# sch1.net
KiCad netlist of a schematic drawn in EAGLE
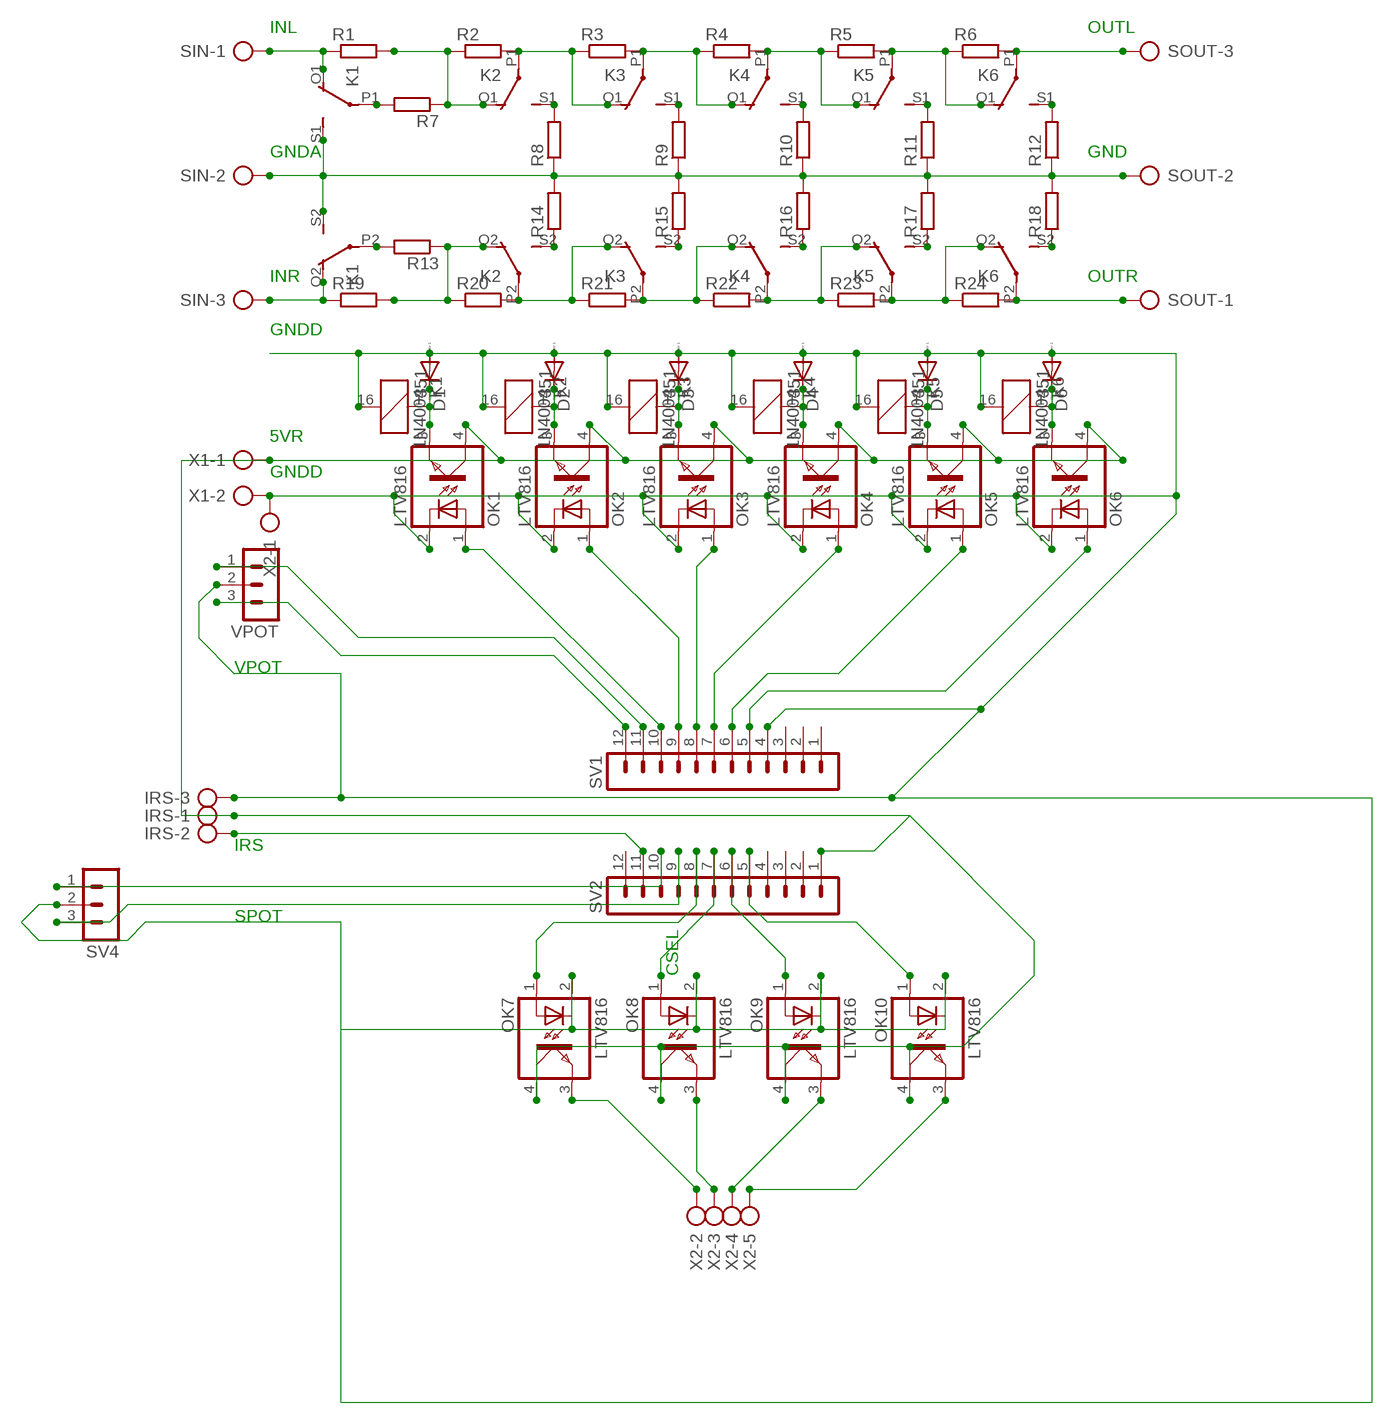
[diagram p0: schematic, sheet 1]

(export (version "E")
  (design (tool "Eeschema 10.0.6"))
  (components
    (comp (ref "D1")
      (value "1N4004")
      (footprint "eagle-import:DO41-10")
      (libsource (lib "eagle-import") (part "1N4004"))
    )
    (comp (ref "D2")
      (value "1N4004")
      (footprint "eagle-import:DO41-10")
      (libsource (lib "eagle-import") (part "1N4004"))
    )
    (comp (ref "D3")
      (value "1N4004")
      (footprint "eagle-import:DO41-10")
      (libsource (lib "eagle-import") (part "1N4004"))
    )
    (comp (ref "D4")
      (value "1N4004")
      (footprint "eagle-import:DO41-10")
      (libsource (lib "eagle-import") (part "1N4004"))
    )
    (comp (ref "D5")
      (value "1N4004")
      (footprint "eagle-import:DO41-10")
      (libsource (lib "eagle-import") (part "1N4004"))
    )
    (comp (ref "D6")
      (value "1N4004")
      (footprint "eagle-import:DO41-10")
      (libsource (lib "eagle-import") (part "1N4004"))
    )
    (comp (ref "IRS")
      (value "AK500/3")
      (footprint "eagle-import:AK500_3")
      (libsource (lib "eagle-import") (part "AK500/3"))
    )
    (comp (ref "K1")
      (value "351")
      (footprint "eagle-import:351")
      (libsource (lib "eagle-import") (part "351"))
    )
    (comp (ref "K2")
      (value "351")
      (footprint "eagle-import:351")
      (libsource (lib "eagle-import") (part "351"))
    )
    (comp (ref "K3")
      (value "351")
      (footprint "eagle-import:351")
      (libsource (lib "eagle-import") (part "351"))
    )
    (comp (ref "K4")
      (value "351")
      (footprint "eagle-import:351")
      (libsource (lib "eagle-import") (part "351"))
    )
    (comp (ref "K5")
      (value "351")
      (footprint "eagle-import:351")
      (libsource (lib "eagle-import") (part "351"))
    )
    (comp (ref "K6")
      (value "351")
      (footprint "eagle-import:351")
      (libsource (lib "eagle-import") (part "351"))
    )
    (comp (ref "OK1")
      (value "LTV816")
      (footprint "eagle-import:DIL04")
      (libsource (lib "eagle-import") (part "LTV816"))
    )
    (comp (ref "OK2")
      (value "LTV816")
      (footprint "eagle-import:DIL04")
      (libsource (lib "eagle-import") (part "LTV816"))
    )
    (comp (ref "OK3")
      (value "LTV816")
      (footprint "eagle-import:DIL04")
      (libsource (lib "eagle-import") (part "LTV816"))
    )
    (comp (ref "OK4")
      (value "LTV816")
      (footprint "eagle-import:DIL04")
      (libsource (lib "eagle-import") (part "LTV816"))
    )
    (comp (ref "OK5")
      (value "LTV816")
      (footprint "eagle-import:DIL04")
      (libsource (lib "eagle-import") (part "LTV816"))
    )
    (comp (ref "OK6")
      (value "LTV816")
      (footprint "eagle-import:DIL04")
      (libsource (lib "eagle-import") (part "LTV816"))
    )
    (comp (ref "OK7")
      (value "LTV816")
      (footprint "eagle-import:DIL04")
      (libsource (lib "eagle-import") (part "LTV816"))
    )
    (comp (ref "OK8")
      (value "LTV816")
      (footprint "eagle-import:DIL04")
      (libsource (lib "eagle-import") (part "LTV816"))
    )
    (comp (ref "OK9")
      (value "LTV816")
      (footprint "eagle-import:DIL04")
      (libsource (lib "eagle-import") (part "LTV816"))
    )
    (comp (ref "OK10")
      (value "LTV816")
      (footprint "eagle-import:DIL04")
      (libsource (lib "eagle-import") (part "LTV816"))
    )
    (comp (ref "R1")
      (value "R-EU_0204/7")
      (footprint "eagle-import:0204_7")
      (libsource (lib "eagle-import") (part "R-EU_0204/7"))
    )
    (comp (ref "R2")
      (value "R-EU_0204/7")
      (footprint "eagle-import:0204_7")
      (libsource (lib "eagle-import") (part "R-EU_0204/7"))
    )
    (comp (ref "R3")
      (value "R-EU_0204/7")
      (footprint "eagle-import:0204_7")
      (libsource (lib "eagle-import") (part "R-EU_0204/7"))
    )
    (comp (ref "R4")
      (value "R-EU_0204/7")
      (footprint "eagle-import:0204_7")
      (libsource (lib "eagle-import") (part "R-EU_0204/7"))
    )
    (comp (ref "R5")
      (value "R-EU_0204/7")
      (footprint "eagle-import:0204_7")
      (libsource (lib "eagle-import") (part "R-EU_0204/7"))
    )
    (comp (ref "R6")
      (value "R-EU_0204/7")
      (footprint "eagle-import:0204_7")
      (libsource (lib "eagle-import") (part "R-EU_0204/7"))
    )
    (comp (ref "R7")
      (value "R-EU_0204/7")
      (footprint "eagle-import:0204_7")
      (libsource (lib "eagle-import") (part "R-EU_0204/7"))
    )
    (comp (ref "R8")
      (value "R-EU_0204/7")
      (footprint "eagle-import:0204_7")
      (libsource (lib "eagle-import") (part "R-EU_0204/7"))
    )
    (comp (ref "R9")
      (value "R-EU_0204/7")
      (footprint "eagle-import:0204_7")
      (libsource (lib "eagle-import") (part "R-EU_0204/7"))
    )
    (comp (ref "R10")
      (value "R-EU_0204/7")
      (footprint "eagle-import:0204_7")
      (libsource (lib "eagle-import") (part "R-EU_0204/7"))
    )
    (comp (ref "R11")
      (value "R-EU_0204/7")
      (footprint "eagle-import:0204_7")
      (libsource (lib "eagle-import") (part "R-EU_0204/7"))
    )
    (comp (ref "R12")
      (value "R-EU_0204/7")
      (footprint "eagle-import:0204_7")
      (libsource (lib "eagle-import") (part "R-EU_0204/7"))
    )
    (comp (ref "R13")
      (value "R-EU_0204/7")
      (footprint "eagle-import:0204_7")
      (libsource (lib "eagle-import") (part "R-EU_0204/7"))
    )
    (comp (ref "R14")
      (value "R-EU_0204/7")
      (footprint "eagle-import:0204_7")
      (libsource (lib "eagle-import") (part "R-EU_0204/7"))
    )
    (comp (ref "R15")
      (value "R-EU_0204/7")
      (footprint "eagle-import:0204_7")
      (libsource (lib "eagle-import") (part "R-EU_0204/7"))
    )
    (comp (ref "R16")
      (value "R-EU_0204/7")
      (footprint "eagle-import:0204_7")
      (libsource (lib "eagle-import") (part "R-EU_0204/7"))
    )
    (comp (ref "R17")
      (value "R-EU_0204/7")
      (footprint "eagle-import:0204_7")
      (libsource (lib "eagle-import") (part "R-EU_0204/7"))
    )
    (comp (ref "R18")
      (value "R-EU_0204/7")
      (footprint "eagle-import:0204_7")
      (libsource (lib "eagle-import") (part "R-EU_0204/7"))
    )
    (comp (ref "R19")
      (value "R-EU_0204/7")
      (footprint "eagle-import:0204_7")
      (libsource (lib "eagle-import") (part "R-EU_0204/7"))
    )
    (comp (ref "R20")
      (value "R-EU_0204/7")
      (footprint "eagle-import:0204_7")
      (libsource (lib "eagle-import") (part "R-EU_0204/7"))
    )
    (comp (ref "R21")
      (value "R-EU_0204/7")
      (footprint "eagle-import:0204_7")
      (libsource (lib "eagle-import") (part "R-EU_0204/7"))
    )
    (comp (ref "R22")
      (value "R-EU_0204/7")
      (footprint "eagle-import:0204_7")
      (libsource (lib "eagle-import") (part "R-EU_0204/7"))
    )
    (comp (ref "R23")
      (value "R-EU_0204/7")
      (footprint "eagle-import:0204_7")
      (libsource (lib "eagle-import") (part "R-EU_0204/7"))
    )
    (comp (ref "R24")
      (value "R-EU_0204/7")
      (footprint "eagle-import:0204_7")
      (libsource (lib "eagle-import") (part "R-EU_0204/7"))
    )
    (comp (ref "SIN")
      (value "AK500/3")
      (footprint "eagle-import:AK500_3")
      (libsource (lib "eagle-import") (part "AK500/3"))
    )
    (comp (ref "SOUT")
      (value "AK500/3")
      (footprint "eagle-import:AK500_3")
      (libsource (lib "eagle-import") (part "AK500/3"))
    )
    (comp (ref "SV1")
      (value "MA12-1")
      (footprint "eagle-import:MA12-1")
      (libsource (lib "eagle-import") (part "MA12-1"))
    )
    (comp (ref "SV2")
      (value "MA12-1")
      (footprint "eagle-import:MA12-1")
      (libsource (lib "eagle-import") (part "MA12-1"))
    )
    (comp (ref "SV4")
      (value "MA03-1")
      (footprint "eagle-import:MA03-1")
      (libsource (lib "eagle-import") (part "MA03-1"))
    )
    (comp (ref "VPOT")
      (value "MA03-1")
      (footprint "eagle-import:MA03-1")
      (libsource (lib "eagle-import") (part "MA03-1"))
    )
    (comp (ref "X1")
      (value "AK500/2")
      (footprint "eagle-import:AK500_2")
      (libsource (lib "eagle-import") (part "AK500/2"))
    )
    (comp (ref "X2")
      (value "AK500/5")
      (footprint "eagle-import:AK500_5")
      (libsource (lib "eagle-import") (part "AK500/5"))
    )
  )
  (nets
    (net (code "1") (name "Net-(IRSA-KL)") (class "Default")
      (node (ref "IRS") (pin "1") (pinfunction "KL_1") (pintype "passive"))
      (node (ref "OK1") (pin "4") (pinfunction "COL_4") (pintype "passive"))
      (node (ref "OK10") (pin "4") (pinfunction "COL_4") (pintype "passive"))
      (node (ref "OK2") (pin "4") (pinfunction "COL_4") (pintype "passive"))
      (node (ref "OK3") (pin "4") (pinfunction "COL_4") (pintype "passive"))
      (node (ref "OK4") (pin "4") (pinfunction "COL_4") (pintype "passive"))
      (node (ref "OK5") (pin "4") (pinfunction "COL_4") (pintype "passive"))
      (node (ref "OK6") (pin "4") (pinfunction "COL_4") (pintype "passive"))
      (node (ref "OK7") (pin "4") (pinfunction "COL_4") (pintype "passive"))
      (node (ref "OK8") (pin "4") (pinfunction "COL_4") (pintype "passive"))
      (node (ref "OK9") (pin "4") (pinfunction "COL_4") (pintype "passive"))
      (node (ref "SV2") (pin "1") (pinfunction "1_1") (pintype "passive"))
      (node (ref "X1") (pin "1") (pinfunction "KL_1") (pintype "passive"))
    )
    (net (code "2") (name "Net-(IRSB-KL)") (class "Default")
      (node (ref "IRS") (pin "2") (pinfunction "KL_2") (pintype "passive"))
      (node (ref "SV2") (pin "11") (pinfunction "11_11") (pintype "passive"))
    )
    (net (code "3") (name "Net-(IRSC-KL)") (class "Default")
      (node (ref "D1") (pin "A") (pinfunction "A_A") (pintype "passive"))
      (node (ref "D2") (pin "A") (pinfunction "A_A") (pintype "passive"))
      (node (ref "D3") (pin "A") (pinfunction "A_A") (pintype "passive"))
      (node (ref "D4") (pin "A") (pinfunction "A_A") (pintype "passive"))
      (node (ref "D5") (pin "A") (pinfunction "A_A") (pintype "passive"))
      (node (ref "D6") (pin "A") (pinfunction "A_A") (pintype "passive"))
      (node (ref "IRS") (pin "3") (pinfunction "KL_3") (pintype "passive"))
      (node (ref "K1") (pin "16") (pinfunction "2_16") (pintype "passive"))
      (node (ref "K2") (pin "16") (pinfunction "2_16") (pintype "passive"))
      (node (ref "K3") (pin "16") (pinfunction "2_16") (pintype "passive"))
      (node (ref "K4") (pin "16") (pinfunction "2_16") (pintype "passive"))
      (node (ref "K5") (pin "16") (pinfunction "2_16") (pintype "passive"))
      (node (ref "K6") (pin "16") (pinfunction "2_16") (pintype "passive"))
      (node (ref "OK1") (pin "2") (pinfunction "C_2") (pintype "passive"))
      (node (ref "OK10") (pin "2") (pinfunction "C_2") (pintype "passive"))
      (node (ref "OK2") (pin "2") (pinfunction "C_2") (pintype "passive"))
      (node (ref "OK3") (pin "2") (pinfunction "C_2") (pintype "passive"))
      (node (ref "OK4") (pin "2") (pinfunction "C_2") (pintype "passive"))
      (node (ref "OK5") (pin "2") (pinfunction "C_2") (pintype "passive"))
      (node (ref "OK6") (pin "2") (pinfunction "C_2") (pintype "passive"))
      (node (ref "OK7") (pin "2") (pinfunction "C_2") (pintype "passive"))
      (node (ref "OK8") (pin "2") (pinfunction "C_2") (pintype "passive"))
      (node (ref "OK9") (pin "2") (pinfunction "C_2") (pintype "passive"))
      (node (ref "SV1") (pin "4") (pinfunction "4_4") (pintype "passive"))
      (node (ref "SV4") (pin "2") (pinfunction "2_2") (pintype "passive"))
      (node (ref "VPOT") (pin "2") (pinfunction "2_2") (pintype "passive"))
      (node (ref "X1") (pin "2") (pinfunction "KL_2") (pintype "passive"))
      (node (ref "X2") (pin "1") (pinfunction "KL_1") (pintype "passive"))
    )
    (net (code "4") (name "Net-(K1B-O)") (class "Default")
      (node (ref "K1") (pin "O1") (pinfunction "O_O1") (pintype "passive"))
      (node (ref "R1") (pin "1") (pinfunction "1_1") (pintype "passive"))
      (node (ref "SIN") (pin "1") (pinfunction "KL_1") (pintype "passive"))
    )
    (net (code "5") (name "Net-(K1B-P)") (class "Default")
      (node (ref "K1") (pin "P1") (pinfunction "P_P1") (pintype "passive"))
      (node (ref "R7") (pin "2") (pinfunction "2_2") (pintype "passive"))
    )
    (net (code "6") (name "Net-(K1B-S)") (class "Default")
      (node (ref "K1") (pin "S1") (pinfunction "S_S1") (pintype "passive"))
      (node (ref "K1") (pin "S2") (pinfunction "S_S2") (pintype "passive"))
      (node (ref "R10") (pin "1") (pinfunction "1_1") (pintype "passive"))
      (node (ref "R11") (pin "1") (pinfunction "1_1") (pintype "passive"))
      (node (ref "R12") (pin "1") (pinfunction "1_1") (pintype "passive"))
      (node (ref "R14") (pin "2") (pinfunction "2_2") (pintype "passive"))
      (node (ref "R15") (pin "2") (pinfunction "2_2") (pintype "passive"))
      (node (ref "R16") (pin "2") (pinfunction "2_2") (pintype "passive"))
      (node (ref "R17") (pin "2") (pinfunction "2_2") (pintype "passive"))
      (node (ref "R18") (pin "2") (pinfunction "2_2") (pintype "passive"))
      (node (ref "R8") (pin "1") (pinfunction "1_1") (pintype "passive"))
      (node (ref "R9") (pin "1") (pinfunction "1_1") (pintype "passive"))
      (node (ref "SIN") (pin "2") (pinfunction "KL_2") (pintype "passive"))
      (node (ref "SOUT") (pin "2") (pinfunction "KL_2") (pintype "passive"))
    )
    (net (code "7") (name "Net-(K1C-O)") (class "Default")
      (node (ref "K1") (pin "O2") (pinfunction "O_O2") (pintype "passive"))
      (node (ref "R19") (pin "1") (pinfunction "1_1") (pintype "passive"))
      (node (ref "SIN") (pin "3") (pinfunction "KL_3") (pintype "passive"))
    )
    (net (code "8") (name "Net-(K1C-P)") (class "Default")
      (node (ref "K1") (pin "P2") (pinfunction "P_P2") (pintype "passive"))
      (node (ref "R13") (pin "2") (pinfunction "2_2") (pintype "passive"))
    )
    (net (code "9") (name "Net-(K2B-O)") (class "Default")
      (node (ref "K2") (pin "O1") (pinfunction "O_O1") (pintype "passive"))
      (node (ref "R1") (pin "2") (pinfunction "2_2") (pintype "passive"))
      (node (ref "R2") (pin "1") (pinfunction "1_1") (pintype "passive"))
      (node (ref "R7") (pin "1") (pinfunction "1_1") (pintype "passive"))
    )
    (net (code "10") (name "Net-(K2B-P)") (class "Default")
      (node (ref "K2") (pin "P1") (pinfunction "P_P1") (pintype "passive"))
      (node (ref "K3") (pin "O1") (pinfunction "O_O1") (pintype "passive"))
      (node (ref "R2") (pin "2") (pinfunction "2_2") (pintype "passive"))
      (node (ref "R3") (pin "1") (pinfunction "1_1") (pintype "passive"))
    )
    (net (code "11") (name "Net-(K2B-S)") (class "Default")
      (node (ref "K2") (pin "S1") (pinfunction "S_S1") (pintype "passive"))
      (node (ref "R8") (pin "2") (pinfunction "2_2") (pintype "passive"))
    )
    (net (code "12") (name "Net-(K2C-O)") (class "Default")
      (node (ref "K2") (pin "O2") (pinfunction "O_O2") (pintype "passive"))
      (node (ref "R13") (pin "1") (pinfunction "1_1") (pintype "passive"))
      (node (ref "R19") (pin "2") (pinfunction "2_2") (pintype "passive"))
      (node (ref "R20") (pin "1") (pinfunction "1_1") (pintype "passive"))
    )
    (net (code "13") (name "Net-(K2C-P)") (class "Default")
      (node (ref "K2") (pin "P2") (pinfunction "P_P2") (pintype "passive"))
      (node (ref "K3") (pin "O2") (pinfunction "O_O2") (pintype "passive"))
      (node (ref "R20") (pin "2") (pinfunction "2_2") (pintype "passive"))
      (node (ref "R21") (pin "1") (pinfunction "1_1") (pintype "passive"))
    )
    (net (code "14") (name "Net-(K2C-S)") (class "Default")
      (node (ref "K2") (pin "S2") (pinfunction "S_S2") (pintype "passive"))
      (node (ref "R14") (pin "1") (pinfunction "1_1") (pintype "passive"))
    )
    (net (code "15") (name "Net-(K3B-P)") (class "Default")
      (node (ref "K3") (pin "P1") (pinfunction "P_P1") (pintype "passive"))
      (node (ref "K4") (pin "O1") (pinfunction "O_O1") (pintype "passive"))
      (node (ref "R3") (pin "2") (pinfunction "2_2") (pintype "passive"))
      (node (ref "R4") (pin "1") (pinfunction "1_1") (pintype "passive"))
    )
    (net (code "16") (name "Net-(K3B-S)") (class "Default")
      (node (ref "K3") (pin "S1") (pinfunction "S_S1") (pintype "passive"))
      (node (ref "R9") (pin "2") (pinfunction "2_2") (pintype "passive"))
    )
    (net (code "17") (name "Net-(K3C-P)") (class "Default")
      (node (ref "K3") (pin "P2") (pinfunction "P_P2") (pintype "passive"))
      (node (ref "K4") (pin "O2") (pinfunction "O_O2") (pintype "passive"))
      (node (ref "R21") (pin "2") (pinfunction "2_2") (pintype "passive"))
      (node (ref "R22") (pin "1") (pinfunction "1_1") (pintype "passive"))
    )
    (net (code "18") (name "Net-(K3C-S)") (class "Default")
      (node (ref "K3") (pin "S2") (pinfunction "S_S2") (pintype "passive"))
      (node (ref "R15") (pin "1") (pinfunction "1_1") (pintype "passive"))
    )
    (net (code "19") (name "Net-(K4B-P)") (class "Default")
      (node (ref "K4") (pin "P1") (pinfunction "P_P1") (pintype "passive"))
      (node (ref "K5") (pin "O1") (pinfunction "O_O1") (pintype "passive"))
      (node (ref "R4") (pin "2") (pinfunction "2_2") (pintype "passive"))
      (node (ref "R5") (pin "1") (pinfunction "1_1") (pintype "passive"))
    )
    (net (code "20") (name "Net-(K4B-S)") (class "Default")
      (node (ref "K4") (pin "S1") (pinfunction "S_S1") (pintype "passive"))
      (node (ref "R10") (pin "2") (pinfunction "2_2") (pintype "passive"))
    )
    (net (code "21") (name "Net-(K4C-P)") (class "Default")
      (node (ref "K4") (pin "P2") (pinfunction "P_P2") (pintype "passive"))
      (node (ref "K5") (pin "O2") (pinfunction "O_O2") (pintype "passive"))
      (node (ref "R22") (pin "2") (pinfunction "2_2") (pintype "passive"))
      (node (ref "R23") (pin "1") (pinfunction "1_1") (pintype "passive"))
    )
    (net (code "22") (name "Net-(K4C-S)") (class "Default")
      (node (ref "K4") (pin "S2") (pinfunction "S_S2") (pintype "passive"))
      (node (ref "R16") (pin "1") (pinfunction "1_1") (pintype "passive"))
    )
    (net (code "23") (name "Net-(K5B-P)") (class "Default")
      (node (ref "K5") (pin "P1") (pinfunction "P_P1") (pintype "passive"))
      (node (ref "K6") (pin "O1") (pinfunction "O_O1") (pintype "passive"))
      (node (ref "R5") (pin "2") (pinfunction "2_2") (pintype "passive"))
      (node (ref "R6") (pin "1") (pinfunction "1_1") (pintype "passive"))
    )
    (net (code "24") (name "Net-(K5B-S)") (class "Default")
      (node (ref "K5") (pin "S1") (pinfunction "S_S1") (pintype "passive"))
      (node (ref "R11") (pin "2") (pinfunction "2_2") (pintype "passive"))
    )
    (net (code "25") (name "Net-(K5C-P)") (class "Default")
      (node (ref "K5") (pin "P2") (pinfunction "P_P2") (pintype "passive"))
      (node (ref "K6") (pin "O2") (pinfunction "O_O2") (pintype "passive"))
      (node (ref "R23") (pin "2") (pinfunction "2_2") (pintype "passive"))
      (node (ref "R24") (pin "1") (pinfunction "1_1") (pintype "passive"))
    )
    (net (code "26") (name "Net-(K5C-S)") (class "Default")
      (node (ref "K5") (pin "S2") (pinfunction "S_S2") (pintype "passive"))
      (node (ref "R17") (pin "1") (pinfunction "1_1") (pintype "passive"))
    )
    (net (code "27") (name "Net-(K6B-P)") (class "Default")
      (node (ref "K6") (pin "P1") (pinfunction "P_P1") (pintype "passive"))
      (node (ref "R6") (pin "2") (pinfunction "2_2") (pintype "passive"))
      (node (ref "SOUT") (pin "3") (pinfunction "KL_3") (pintype "passive"))
    )
    (net (code "28") (name "Net-(K6B-S)") (class "Default")
      (node (ref "K6") (pin "S1") (pinfunction "S_S1") (pintype "passive"))
      (node (ref "R12") (pin "2") (pinfunction "2_2") (pintype "passive"))
    )
    (net (code "29") (name "Net-(K6C-P)") (class "Default")
      (node (ref "K6") (pin "P2") (pinfunction "P_P2") (pintype "passive"))
      (node (ref "R24") (pin "2") (pinfunction "2_2") (pintype "passive"))
      (node (ref "SOUT") (pin "1") (pinfunction "KL_1") (pintype "passive"))
    )
    (net (code "30") (name "Net-(K6C-S)") (class "Default")
      (node (ref "K6") (pin "S2") (pinfunction "S_S2") (pintype "passive"))
      (node (ref "R18") (pin "1") (pinfunction "1_1") (pintype "passive"))
    )
    (net (code "31") (name "Net-(OK1-A)") (class "Default")
      (node (ref "OK1") (pin "1") (pinfunction "A_1") (pintype "passive"))
      (node (ref "SV1") (pin "10") (pinfunction "10_10") (pintype "passive"))
    )
    (net (code "32") (name "Net-(OK1-EMIT)") (class "Default")
      (node (ref "D1") (pin "C") (pinfunction "C_C") (pintype "passive"))
      (node (ref "K1") (pin "1") (pinfunction "1_1") (pintype "passive"))
      (node (ref "OK1") (pin "3") (pinfunction "EMIT_3") (pintype "passive"))
    )
    (net (code "33") (name "Net-(OK2-A)") (class "Default")
      (node (ref "OK2") (pin "1") (pinfunction "A_1") (pintype "passive"))
      (node (ref "SV1") (pin "9") (pinfunction "9_9") (pintype "passive"))
    )
    (net (code "34") (name "Net-(OK2-EMIT)") (class "Default")
      (node (ref "D2") (pin "C") (pinfunction "C_C") (pintype "passive"))
      (node (ref "K2") (pin "1") (pinfunction "1_1") (pintype "passive"))
      (node (ref "OK2") (pin "3") (pinfunction "EMIT_3") (pintype "passive"))
    )
    (net (code "35") (name "Net-(OK3-A)") (class "Default")
      (node (ref "OK3") (pin "1") (pinfunction "A_1") (pintype "passive"))
      (node (ref "SV1") (pin "8") (pinfunction "8_8") (pintype "passive"))
    )
    (net (code "36") (name "Net-(OK3-EMIT)") (class "Default")
      (node (ref "D3") (pin "C") (pinfunction "C_C") (pintype "passive"))
      (node (ref "K3") (pin "1") (pinfunction "1_1") (pintype "passive"))
      (node (ref "OK3") (pin "3") (pinfunction "EMIT_3") (pintype "passive"))
    )
    (net (code "37") (name "Net-(OK4-A)") (class "Default")
      (node (ref "OK4") (pin "1") (pinfunction "A_1") (pintype "passive"))
      (node (ref "SV1") (pin "7") (pinfunction "7_7") (pintype "passive"))
    )
    (net (code "38") (name "Net-(OK4-EMIT)") (class "Default")
      (node (ref "D4") (pin "C") (pinfunction "C_C") (pintype "passive"))
      (node (ref "K4") (pin "1") (pinfunction "1_1") (pintype "passive"))
      (node (ref "OK4") (pin "3") (pinfunction "EMIT_3") (pintype "passive"))
    )
    (net (code "39") (name "Net-(OK5-A)") (class "Default")
      (node (ref "OK5") (pin "1") (pinfunction "A_1") (pintype "passive"))
      (node (ref "SV1") (pin "6") (pinfunction "6_6") (pintype "passive"))
    )
    (net (code "40") (name "Net-(OK5-EMIT)") (class "Default")
      (node (ref "D5") (pin "C") (pinfunction "C_C") (pintype "passive"))
      (node (ref "K5") (pin "1") (pinfunction "1_1") (pintype "passive"))
      (node (ref "OK5") (pin "3") (pinfunction "EMIT_3") (pintype "passive"))
    )
    (net (code "41") (name "Net-(OK6-A)") (class "Default")
      (node (ref "OK6") (pin "1") (pinfunction "A_1") (pintype "passive"))
      (node (ref "SV1") (pin "5") (pinfunction "5_5") (pintype "passive"))
    )
    (net (code "42") (name "Net-(OK6-EMIT)") (class "Default")
      (node (ref "D6") (pin "C") (pinfunction "C_C") (pintype "passive"))
      (node (ref "K6") (pin "1") (pinfunction "1_1") (pintype "passive"))
      (node (ref "OK6") (pin "3") (pinfunction "EMIT_3") (pintype "passive"))
    )
    (net (code "43") (name "Net-(OK7-A)") (class "Default")
      (node (ref "OK7") (pin "1") (pinfunction "A_1") (pintype "passive"))
      (node (ref "SV2") (pin "8") (pinfunction "8_8") (pintype "passive"))
    )
    (net (code "44") (name "Net-(OK7-EMIT)") (class "Default")
      (node (ref "OK7") (pin "3") (pinfunction "EMIT_3") (pintype "passive"))
      (node (ref "X2") (pin "2") (pinfunction "KL_2") (pintype "passive"))
    )
    (net (code "45") (name "Net-(OK8-A)") (class "Default")
      (node (ref "OK8") (pin "1") (pinfunction "A_1") (pintype "passive"))
      (node (ref "SV2") (pin "7") (pinfunction "7_7") (pintype "passive"))
    )
    (net (code "46") (name "Net-(OK8-EMIT)") (class "Default")
      (node (ref "OK8") (pin "3") (pinfunction "EMIT_3") (pintype "passive"))
      (node (ref "X2") (pin "3") (pinfunction "KL_3") (pintype "passive"))
    )
    (net (code "47") (name "Net-(OK9-A)") (class "Default")
      (node (ref "OK9") (pin "1") (pinfunction "A_1") (pintype "passive"))
      (node (ref "SV2") (pin "6") (pinfunction "6_6") (pintype "passive"))
    )
    (net (code "48") (name "Net-(OK9-EMIT)") (class "Default")
      (node (ref "OK9") (pin "3") (pinfunction "EMIT_3") (pintype "passive"))
      (node (ref "X2") (pin "4") (pinfunction "KL_4") (pintype "passive"))
    )
    (net (code "49") (name "Net-(OK10-A)") (class "Default")
      (node (ref "OK10") (pin "1") (pinfunction "A_1") (pintype "passive"))
      (node (ref "SV2") (pin "5") (pinfunction "5_5") (pintype "passive"))
    )
    (net (code "50") (name "Net-(OK10-EMIT)") (class "Default")
      (node (ref "OK10") (pin "3") (pinfunction "EMIT_3") (pintype "passive"))
      (node (ref "X2") (pin "5") (pinfunction "KL_5") (pintype "passive"))
    )
    (net (code "51") (name "Net-(SV1-Pad11)") (class "Default")
      (node (ref "SV1") (pin "11") (pinfunction "11_11") (pintype "passive"))
      (node (ref "VPOT") (pin "1") (pinfunction "1_1") (pintype "passive"))
    )
    (net (code "52") (name "Net-(SV1-Pad12)") (class "Default")
      (node (ref "SV1") (pin "12") (pinfunction "12_12") (pintype "passive"))
      (node (ref "VPOT") (pin "3") (pinfunction "3_3") (pintype "passive"))
    )
    (net (code "53") (name "Net-(SV2-Pad9)") (class "Default")
      (node (ref "SV2") (pin "9") (pinfunction "9_9") (pintype "passive"))
      (node (ref "SV4") (pin "3") (pinfunction "3_3") (pintype "passive"))
    )
    (net (code "54") (name "Net-(SV2-Pad10)") (class "Default")
      (node (ref "SV2") (pin "10") (pinfunction "10_10") (pintype "passive"))
      (node (ref "SV4") (pin "1") (pinfunction "1_1") (pintype "passive"))
    )
    (net (code "55") (name "unconnected-(SV1-Pad1)") (class "Default")
      (node (ref "SV1") (pin "1") (pinfunction "1_1") (pintype "passive"))
    )
    (net (code "56") (name "unconnected-(SV1-Pad2)") (class "Default")
      (node (ref "SV1") (pin "2") (pinfunction "2_2") (pintype "passive"))
    )
    (net (code "57") (name "unconnected-(SV1-Pad3)") (class "Default")
      (node (ref "SV1") (pin "3") (pinfunction "3_3") (pintype "passive"))
    )
    (net (code "58") (name "unconnected-(SV2-Pad2)") (class "Default")
      (node (ref "SV2") (pin "2") (pinfunction "2_2") (pintype "passive"))
    )
    (net (code "59") (name "unconnected-(SV2-Pad3)") (class "Default")
      (node (ref "SV2") (pin "3") (pinfunction "3_3") (pintype "passive"))
    )
    (net (code "60") (name "unconnected-(SV2-Pad4)") (class "Default")
      (node (ref "SV2") (pin "4") (pinfunction "4_4") (pintype "passive"))
    )
    (net (code "61") (name "unconnected-(SV2-Pad12)") (class "Default")
      (node (ref "SV2") (pin "12") (pinfunction "12_12") (pintype "passive"))
    )
  )
)
